# Cherry_MX.net
KiCad netlist of a schematic drawn in Altium Designer
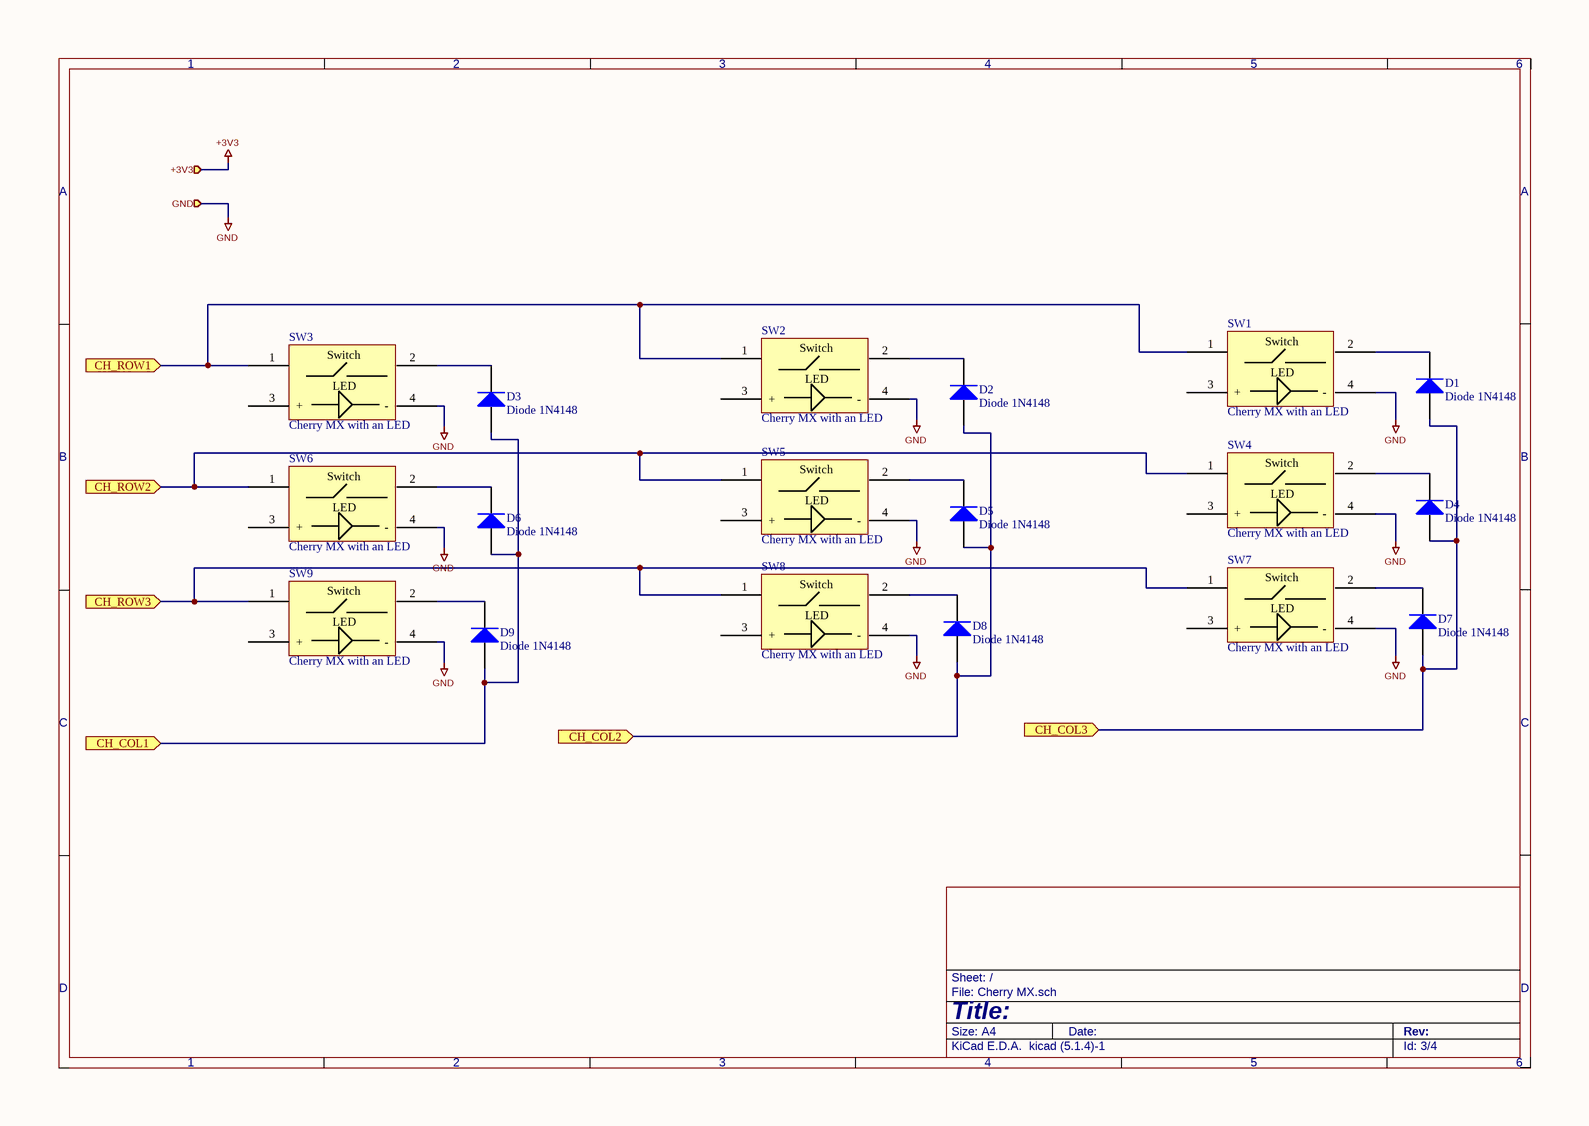
[diagram p0: Cherry MX.SchDoc]

(export (version "E")
  (design (tool "Eeschema 10.0.6"))
  (components
    (comp (ref "D1")
      (value "Diode 1N4148")
      (footprint "DO-35")
      (description "High Conductance Fast Diode")
      (fields (field (name "PUBLISHER") "Altium Limited"))
      (libsource (lib "Miscellaneous Devices") (part "Diode 1N4148"))
    )
    (comp (ref "D2")
      (value "Diode 1N4148")
      (footprint "DO-35")
      (description "High Conductance Fast Diode")
      (fields (field (name "PUBLISHER") "Altium Limited"))
      (libsource (lib "Miscellaneous Devices") (part "Diode 1N4148"))
    )
    (comp (ref "D3")
      (value "Diode 1N4148")
      (footprint "DO-35")
      (description "High Conductance Fast Diode")
      (fields (field (name "PUBLISHER") "Altium Limited"))
      (libsource (lib "Miscellaneous Devices") (part "Diode 1N4148"))
    )
    (comp (ref "D4")
      (value "Diode 1N4148")
      (footprint "DO-35")
      (description "High Conductance Fast Diode")
      (fields (field (name "PUBLISHER") "Altium Limited"))
      (libsource (lib "Miscellaneous Devices") (part "Diode 1N4148"))
    )
    (comp (ref "D5")
      (value "Diode 1N4148")
      (footprint "DO-35")
      (description "High Conductance Fast Diode")
      (fields (field (name "PUBLISHER") "Altium Limited"))
      (libsource (lib "Miscellaneous Devices") (part "Diode 1N4148"))
    )
    (comp (ref "D6")
      (value "Diode 1N4148")
      (footprint "DO-35")
      (description "High Conductance Fast Diode")
      (fields (field (name "PUBLISHER") "Altium Limited"))
      (libsource (lib "Miscellaneous Devices") (part "Diode 1N4148"))
    )
    (comp (ref "D7")
      (value "Diode 1N4148")
      (footprint "DO-35")
      (description "High Conductance Fast Diode")
      (fields (field (name "PUBLISHER") "Altium Limited"))
      (libsource (lib "Miscellaneous Devices") (part "Diode 1N4148"))
    )
    (comp (ref "D8")
      (value "Diode 1N4148")
      (footprint "DO-35")
      (description "High Conductance Fast Diode")
      (fields (field (name "PUBLISHER") "Altium Limited"))
      (libsource (lib "Miscellaneous Devices") (part "Diode 1N4148"))
    )
    (comp (ref "D9")
      (value "Diode 1N4148")
      (footprint "DO-35")
      (description "High Conductance Fast Diode")
      (fields (field (name "PUBLISHER") "Altium Limited"))
      (libsource (lib "Miscellaneous Devices") (part "Diode 1N4148"))
    )
    (comp (ref "SW1")
      (value "Cherry MX with an LED")
      (footprint "MX_Cherry_LED")
      (libsource (lib "PlumPot_Library") (part "MX_Cherry_LED"))
    )
    (comp (ref "SW2")
      (value "Cherry MX with an LED")
      (footprint "MX_Cherry_LED")
      (libsource (lib "PlumPot_Library") (part "MX_Cherry_LED"))
    )
    (comp (ref "SW3")
      (value "Cherry MX with an LED")
      (footprint "MX_Cherry_LED")
      (libsource (lib "PlumPot_Library") (part "MX_Cherry_LED"))
    )
    (comp (ref "SW4")
      (value "Cherry MX with an LED")
      (footprint "MX_Cherry_LED")
      (libsource (lib "PlumPot_Library") (part "MX_Cherry_LED"))
    )
    (comp (ref "SW5")
      (value "Cherry MX with an LED")
      (footprint "MX_Cherry_LED")
      (libsource (lib "PlumPot_Library") (part "MX_Cherry_LED"))
    )
    (comp (ref "SW6")
      (value "Cherry MX with an LED")
      (footprint "MX_Cherry_LED")
      (libsource (lib "PlumPot_Library") (part "MX_Cherry_LED"))
    )
    (comp (ref "SW7")
      (value "Cherry MX with an LED")
      (footprint "MX_Cherry_LED")
      (libsource (lib "PlumPot_Library") (part "MX_Cherry_LED"))
    )
    (comp (ref "SW8")
      (value "Cherry MX with an LED")
      (footprint "MX_Cherry_LED")
      (libsource (lib "PlumPot_Library") (part "MX_Cherry_LED"))
    )
    (comp (ref "SW9")
      (value "Cherry MX with an LED")
      (footprint "MX_Cherry_LED")
      (libsource (lib "PlumPot_Library") (part "MX_Cherry_LED"))
    )
  )
  (nets
    (net (code "2") (name "/CH_COL1") (class "Default")
      (node (ref "D3") (pin "1") (pinfunction "A_1") (pintype "passive"))
      (node (ref "D6") (pin "1") (pinfunction "A_1") (pintype "passive"))
      (node (ref "D9") (pin "1") (pinfunction "A_1") (pintype "passive"))
    )
    (net (code "3") (name "/CH_COL2") (class "Default")
      (node (ref "D2") (pin "1") (pinfunction "A_1") (pintype "passive"))
      (node (ref "D5") (pin "1") (pinfunction "A_1") (pintype "passive"))
      (node (ref "D8") (pin "1") (pinfunction "A_1") (pintype "passive"))
    )
    (net (code "4") (name "/CH_COL3") (class "Default")
      (node (ref "D1") (pin "1") (pinfunction "A_1") (pintype "passive"))
      (node (ref "D4") (pin "1") (pinfunction "A_1") (pintype "passive"))
      (node (ref "D7") (pin "1") (pinfunction "A_1") (pintype "passive"))
    )
    (net (code "5") (name "/CH_ROW1") (class "Default")
      (node (ref "SW1") (pin "1") (pintype "passive"))
      (node (ref "SW2") (pin "1") (pintype "passive"))
      (node (ref "SW3") (pin "1") (pintype "passive"))
    )
    (net (code "6") (name "/CH_ROW2") (class "Default")
      (node (ref "SW4") (pin "1") (pintype "passive"))
      (node (ref "SW5") (pin "1") (pintype "passive"))
      (node (ref "SW6") (pin "1") (pintype "passive"))
    )
    (net (code "7") (name "/CH_ROW3") (class "Default")
      (node (ref "SW7") (pin "1") (pintype "passive"))
      (node (ref "SW8") (pin "1") (pintype "passive"))
      (node (ref "SW9") (pin "1") (pintype "passive"))
    )
    (net (code "8") (name "GND") (class "Default")
      (node (ref "SW1") (pin "4") (pinfunction "-_4") (pintype "passive"))
      (node (ref "SW2") (pin "4") (pinfunction "-_4") (pintype "passive"))
      (node (ref "SW3") (pin "4") (pinfunction "-_4") (pintype "passive"))
      (node (ref "SW4") (pin "4") (pinfunction "-_4") (pintype "passive"))
      (node (ref "SW5") (pin "4") (pinfunction "-_4") (pintype "passive"))
      (node (ref "SW6") (pin "4") (pinfunction "-_4") (pintype "passive"))
      (node (ref "SW7") (pin "4") (pinfunction "-_4") (pintype "passive"))
      (node (ref "SW8") (pin "4") (pinfunction "-_4") (pintype "passive"))
      (node (ref "SW9") (pin "4") (pinfunction "-_4") (pintype "passive"))
    )
    (net (code "9") (name "Net-(D1-K)") (class "Default")
      (node (ref "D1") (pin "2") (pinfunction "K_2") (pintype "passive"))
      (node (ref "SW1") (pin "2") (pintype "passive"))
    )
    (net (code "10") (name "Net-(D2-K)") (class "Default")
      (node (ref "D2") (pin "2") (pinfunction "K_2") (pintype "passive"))
      (node (ref "SW2") (pin "2") (pintype "passive"))
    )
    (net (code "11") (name "Net-(D3-K)") (class "Default")
      (node (ref "D3") (pin "2") (pinfunction "K_2") (pintype "passive"))
      (node (ref "SW3") (pin "2") (pintype "passive"))
    )
    (net (code "12") (name "Net-(D4-K)") (class "Default")
      (node (ref "D4") (pin "2") (pinfunction "K_2") (pintype "passive"))
      (node (ref "SW4") (pin "2") (pintype "passive"))
    )
    (net (code "13") (name "Net-(D5-K)") (class "Default")
      (node (ref "D5") (pin "2") (pinfunction "K_2") (pintype "passive"))
      (node (ref "SW5") (pin "2") (pintype "passive"))
    )
    (net (code "14") (name "Net-(D6-K)") (class "Default")
      (node (ref "D6") (pin "2") (pinfunction "K_2") (pintype "passive"))
      (node (ref "SW6") (pin "2") (pintype "passive"))
    )
    (net (code "15") (name "Net-(D7-K)") (class "Default")
      (node (ref "D7") (pin "2") (pinfunction "K_2") (pintype "passive"))
      (node (ref "SW7") (pin "2") (pintype "passive"))
    )
    (net (code "16") (name "Net-(D8-K)") (class "Default")
      (node (ref "D8") (pin "2") (pinfunction "K_2") (pintype "passive"))
      (node (ref "SW8") (pin "2") (pintype "passive"))
    )
    (net (code "17") (name "Net-(D9-K)") (class "Default")
      (node (ref "D9") (pin "2") (pinfunction "K_2") (pintype "passive"))
      (node (ref "SW9") (pin "2") (pintype "passive"))
    )
    (net (code "18") (name "unconnected-(SW1-+-Pad3)") (class "Default")
      (node (ref "SW1") (pin "3") (pinfunction "+_3") (pintype "passive"))
    )
    (net (code "19") (name "unconnected-(SW2-+-Pad3)") (class "Default")
      (node (ref "SW2") (pin "3") (pinfunction "+_3") (pintype "passive"))
    )
    (net (code "20") (name "unconnected-(SW3-+-Pad3)") (class "Default")
      (node (ref "SW3") (pin "3") (pinfunction "+_3") (pintype "passive"))
    )
    (net (code "21") (name "unconnected-(SW4-+-Pad3)") (class "Default")
      (node (ref "SW4") (pin "3") (pinfunction "+_3") (pintype "passive"))
    )
    (net (code "22") (name "unconnected-(SW5-+-Pad3)") (class "Default")
      (node (ref "SW5") (pin "3") (pinfunction "+_3") (pintype "passive"))
    )
    (net (code "23") (name "unconnected-(SW6-+-Pad3)") (class "Default")
      (node (ref "SW6") (pin "3") (pinfunction "+_3") (pintype "passive"))
    )
    (net (code "24") (name "unconnected-(SW7-+-Pad3)") (class "Default")
      (node (ref "SW7") (pin "3") (pinfunction "+_3") (pintype "passive"))
    )
    (net (code "25") (name "unconnected-(SW8-+-Pad3)") (class "Default")
      (node (ref "SW8") (pin "3") (pinfunction "+_3") (pintype "passive"))
    )
    (net (code "26") (name "unconnected-(SW9-+-Pad3)") (class "Default")
      (node (ref "SW9") (pin "3") (pinfunction "+_3") (pintype "passive"))
    )
  )
)
